# RAM.net
KiCad netlist of a schematic drawn in EAGLE
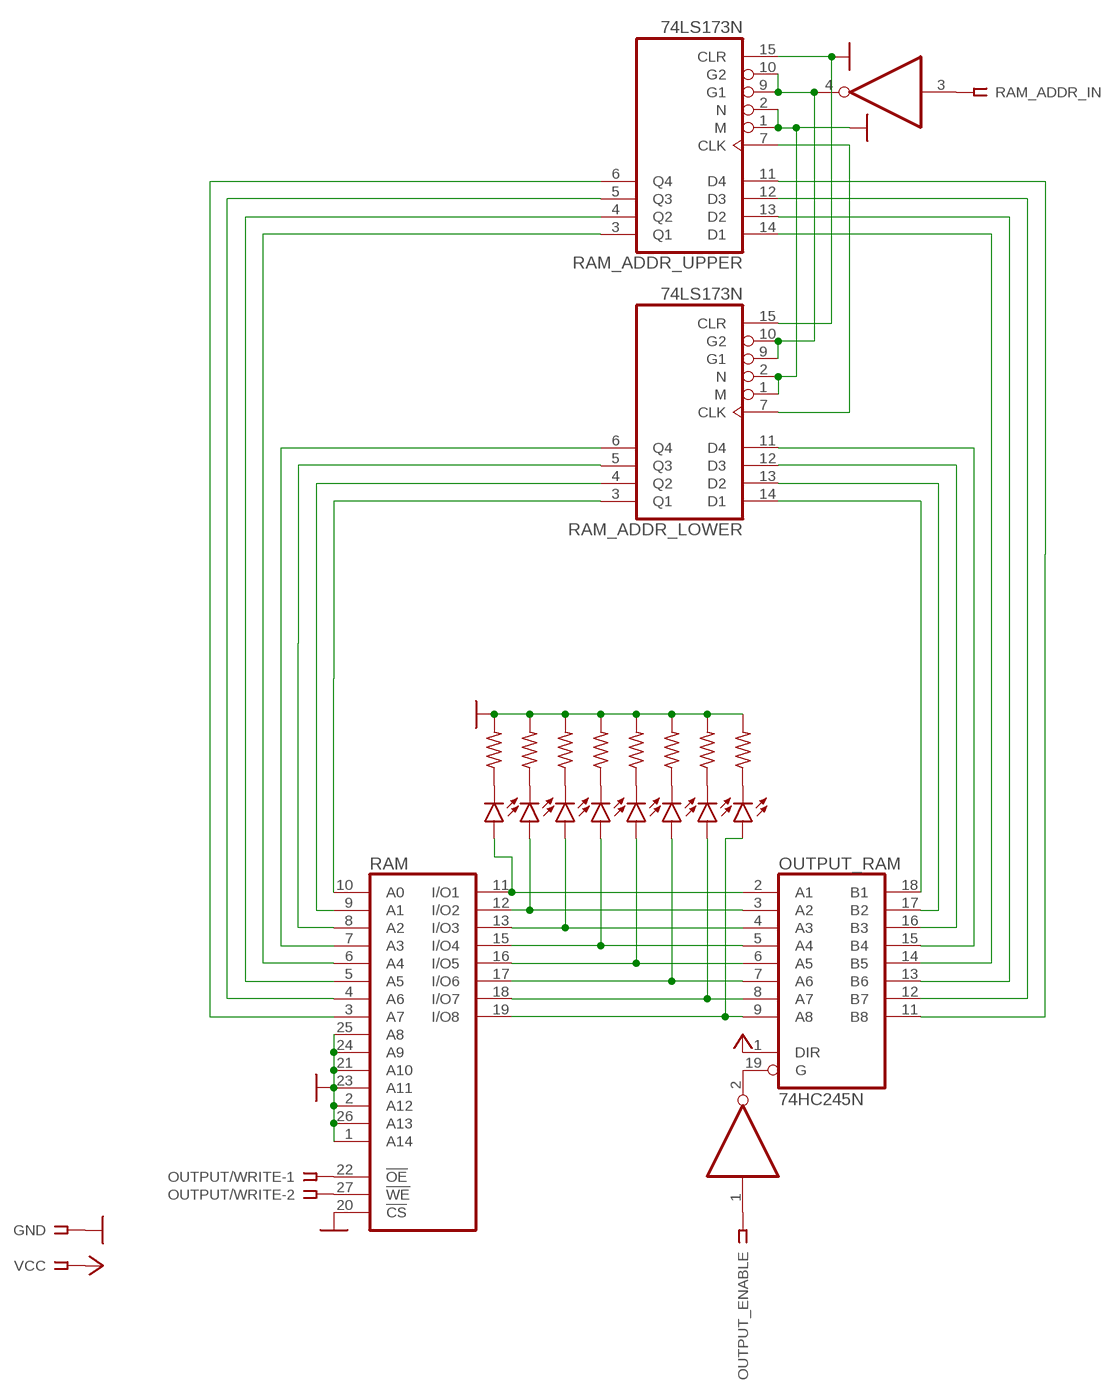
[diagram p0: schematic, sheet 1]

(export (version "E")
  (design (tool "Eeschema 10.0.6"))
  (components
    (comp (ref "GND")
      (value "SSW-101-02-G-S-RA")
      (footprint "eagle-import:SSW-101-02-G-S-RA")
      (fields (field (name "MF") "Samtec Inc."))
      (libsource (lib "eagle-import") (part "SSW-101-02-G-S-RA"))
    )
    (comp (ref "LED1")
      (value "LED3MM")
      (footprint "eagle-import:LED3MM")
      (libsource (lib "eagle-import") (part "LED3MM"))
    )
    (comp (ref "LED2")
      (value "LED3MM")
      (footprint "eagle-import:LED3MM")
      (libsource (lib "eagle-import") (part "LED3MM"))
    )
    (comp (ref "LED3")
      (value "LED3MM")
      (footprint "eagle-import:LED3MM")
      (libsource (lib "eagle-import") (part "LED3MM"))
    )
    (comp (ref "LED4")
      (value "LED3MM")
      (footprint "eagle-import:LED3MM")
      (libsource (lib "eagle-import") (part "LED3MM"))
    )
    (comp (ref "LED5")
      (value "LED3MM")
      (footprint "eagle-import:LED3MM")
      (libsource (lib "eagle-import") (part "LED3MM"))
    )
    (comp (ref "LED6")
      (value "LED3MM")
      (footprint "eagle-import:LED3MM")
      (libsource (lib "eagle-import") (part "LED3MM"))
    )
    (comp (ref "LED7")
      (value "LED3MM")
      (footprint "eagle-import:LED3MM")
      (libsource (lib "eagle-import") (part "LED3MM"))
    )
    (comp (ref "LED8")
      (value "LED3MM")
      (footprint "eagle-import:LED3MM")
      (libsource (lib "eagle-import") (part "LED3MM"))
    )
    (comp (ref "NOT_GATE")
      (value "74LS04N")
      (footprint "eagle-import:DIL14")
      (libsource (lib "eagle-import") (part "7404NLS"))
    )
    (comp (ref "OUTPUT/WRITE")
      (value "SSW-102-02-G-S")
      (footprint "eagle-import:SSW-102-02-G-S")
      (fields (field (name "MF") "Samtec Inc."))
      (libsource (lib "eagle-import") (part "SSW-102-02-G-S"))
    )
    (comp (ref "OUTPUT_ENABLE")
      (value "SSW-101-02-G-S")
      (footprint "eagle-import:SSW-101-02-G-S")
      (fields (field (name "MF") "Samtec Inc."))
      (libsource (lib "eagle-import") (part "SSW-101-02-G-S"))
    )
    (comp (ref "OUTPUT_RAM")
      (value "74HC245N")
      (footprint "eagle-import:DIL20")
      (libsource (lib "eagle-import") (part "74245NHC"))
    )
    (comp (ref "R1")
      (value "R-US_0204/7")
      (footprint "eagle-import:0204_7")
      (libsource (lib "eagle-import") (part "R-US_0204/7"))
    )
    (comp (ref "R2")
      (value "R-US_0204/7")
      (footprint "eagle-import:0204_7")
      (libsource (lib "eagle-import") (part "R-US_0204/7"))
    )
    (comp (ref "R3")
      (value "R-US_0204/7")
      (footprint "eagle-import:0204_7")
      (libsource (lib "eagle-import") (part "R-US_0204/7"))
    )
    (comp (ref "R4")
      (value "R-US_0204/7")
      (footprint "eagle-import:0204_7")
      (libsource (lib "eagle-import") (part "R-US_0204/7"))
    )
    (comp (ref "R5")
      (value "R-US_0204/7")
      (footprint "eagle-import:0204_7")
      (libsource (lib "eagle-import") (part "R-US_0204/7"))
    )
    (comp (ref "R6")
      (value "R-US_0204/7")
      (footprint "eagle-import:0204_7")
      (libsource (lib "eagle-import") (part "R-US_0204/7"))
    )
    (comp (ref "R7")
      (value "R-US_0204/7")
      (footprint "eagle-import:0204_7")
      (libsource (lib "eagle-import") (part "R-US_0204/7"))
    )
    (comp (ref "R8")
      (value "R-US_0204/7")
      (footprint "eagle-import:0204_7")
      (libsource (lib "eagle-import") (part "R-US_0204/7"))
    )
    (comp (ref "RAM")
      (value "71256P")
      (footprint "eagle-import:DIL28-6")
      (libsource (lib "eagle-import") (part "71256P"))
    )
    (comp (ref "RAM_ADDR_IN")
      (value "SSW-101-02-G-S")
      (footprint "eagle-import:SSW-101-02-G-S")
      (fields (field (name "MF") "Samtec Inc."))
      (libsource (lib "eagle-import") (part "SSW-101-02-G-S"))
    )
    (comp (ref "RAM_ADDR_LOWER")
      (value "74LS173N")
      (footprint "eagle-import:DIL16")
      (libsource (lib "eagle-import") (part "74173NLS"))
    )
    (comp (ref "RAM_ADDR_UPPER")
      (value "74LS173N")
      (footprint "eagle-import:DIL16")
      (libsource (lib "eagle-import") (part "74173NLS"))
    )
    (comp (ref "VCC")
      (value "SSW-101-02-G-S-RA")
      (footprint "eagle-import:SSW-101-02-G-S-RA")
      (fields (field (name "MF") "Samtec Inc."))
      (libsource (lib "eagle-import") (part "SSW-101-02-G-S-RA"))
    )
  )
  (nets
    (net (code "1") (name "GND") (class "Default")
      (node (ref "GND") (pin "1") (pinfunction "1_1") (pintype "passive"))
      (node (ref "R1") (pin "2") (pinfunction "2_2") (pintype "passive"))
      (node (ref "R2") (pin "2") (pinfunction "2_2") (pintype "passive"))
      (node (ref "R3") (pin "2") (pinfunction "2_2") (pintype "passive"))
      (node (ref "R4") (pin "2") (pinfunction "2_2") (pintype "passive"))
      (node (ref "R5") (pin "2") (pinfunction "2_2") (pintype "passive"))
      (node (ref "R6") (pin "2") (pinfunction "2_2") (pintype "passive"))
      (node (ref "R7") (pin "2") (pinfunction "2_2") (pintype "passive"))
      (node (ref "R8") (pin "2") (pinfunction "2_2") (pintype "passive"))
      (node (ref "RAM") (pin "1") (pinfunction "A14_1") (pintype "input"))
      (node (ref "RAM") (pin "2") (pinfunction "A12_2") (pintype "input"))
      (node (ref "RAM") (pin "20") (pinfunction "~{CS}_20") (pintype "input"))
      (node (ref "RAM") (pin "21") (pinfunction "A10_21") (pintype "input"))
      (node (ref "RAM") (pin "23") (pinfunction "A11_23") (pintype "input"))
      (node (ref "RAM") (pin "24") (pinfunction "A9_24") (pintype "input"))
      (node (ref "RAM") (pin "25") (pinfunction "A8_25") (pintype "input"))
      (node (ref "RAM") (pin "26") (pinfunction "A13_26") (pintype "input"))
      (node (ref "RAM_ADDR_LOWER") (pin "1") (pinfunction "M_1") (pintype "input"))
      (node (ref "RAM_ADDR_LOWER") (pin "15") (pinfunction "CLR_15") (pintype "input"))
      (node (ref "RAM_ADDR_LOWER") (pin "2") (pinfunction "N_2") (pintype "input"))
      (node (ref "RAM_ADDR_UPPER") (pin "1") (pinfunction "M_1") (pintype "input"))
      (node (ref "RAM_ADDR_UPPER") (pin "15") (pinfunction "CLR_15") (pintype "input"))
      (node (ref "RAM_ADDR_UPPER") (pin "2") (pinfunction "N_2") (pintype "input"))
    )
    (net (code "2") (name "Net-(LED1-C)") (class "Default")
      (node (ref "LED1") (pin "K") (pinfunction "C_K") (pintype "passive"))
      (node (ref "R1") (pin "1") (pinfunction "1_1") (pintype "passive"))
    )
    (net (code "3") (name "Net-(LED2-C)") (class "Default")
      (node (ref "LED2") (pin "K") (pinfunction "C_K") (pintype "passive"))
      (node (ref "R2") (pin "1") (pinfunction "1_1") (pintype "passive"))
    )
    (net (code "4") (name "Net-(LED3-C)") (class "Default")
      (node (ref "LED3") (pin "K") (pinfunction "C_K") (pintype "passive"))
      (node (ref "R3") (pin "1") (pinfunction "1_1") (pintype "passive"))
    )
    (net (code "5") (name "Net-(LED4-C)") (class "Default")
      (node (ref "LED4") (pin "K") (pinfunction "C_K") (pintype "passive"))
      (node (ref "R4") (pin "1") (pinfunction "1_1") (pintype "passive"))
    )
    (net (code "6") (name "Net-(LED5-C)") (class "Default")
      (node (ref "LED5") (pin "K") (pinfunction "C_K") (pintype "passive"))
      (node (ref "R5") (pin "1") (pinfunction "1_1") (pintype "passive"))
    )
    (net (code "7") (name "Net-(LED6-C)") (class "Default")
      (node (ref "LED6") (pin "K") (pinfunction "C_K") (pintype "passive"))
      (node (ref "R6") (pin "1") (pinfunction "1_1") (pintype "passive"))
    )
    (net (code "8") (name "Net-(LED7-C)") (class "Default")
      (node (ref "LED7") (pin "K") (pinfunction "C_K") (pintype "passive"))
      (node (ref "R7") (pin "1") (pinfunction "1_1") (pintype "passive"))
    )
    (net (code "9") (name "Net-(LED8-C)") (class "Default")
      (node (ref "LED8") (pin "K") (pinfunction "C_K") (pintype "passive"))
      (node (ref "R8") (pin "1") (pinfunction "1_1") (pintype "passive"))
    )
    (net (code "10") (name "Net-(NOT_GATEA-I)") (class "Default")
      (node (ref "NOT_GATE") (pin "1") (pinfunction "I_1") (pintype "input"))
      (node (ref "OUTPUT_ENABLE") (pin "1") (pinfunction "1_1") (pintype "passive"))
    )
    (net (code "11") (name "Net-(NOT_GATEA-O)") (class "Default")
      (node (ref "NOT_GATE") (pin "2") (pinfunction "O_2") (pintype "output"))
      (node (ref "OUTPUT_RAM") (pin "19") (pinfunction "G_19") (pintype "input"))
    )
    (net (code "12") (name "Net-(NOT_GATEB-I)") (class "Default")
      (node (ref "NOT_GATE") (pin "3") (pinfunction "I_3") (pintype "input"))
      (node (ref "RAM_ADDR_IN") (pin "1") (pinfunction "1_1") (pintype "passive"))
    )
    (net (code "13") (name "Net-(NOT_GATEB-O)") (class "Default")
      (node (ref "NOT_GATE") (pin "4") (pinfunction "O_4") (pintype "output"))
      (node (ref "RAM_ADDR_LOWER") (pin "10") (pinfunction "G2_10") (pintype "input"))
      (node (ref "RAM_ADDR_LOWER") (pin "9") (pinfunction "G1_9") (pintype "input"))
      (node (ref "RAM_ADDR_UPPER") (pin "10") (pinfunction "G2_10") (pintype "input"))
      (node (ref "RAM_ADDR_UPPER") (pin "9") (pinfunction "G1_9") (pintype "input"))
    )
    (net (code "14") (name "Net-(OUTPUT/WRITEB-1)") (class "Default")
      (node (ref "OUTPUT/WRITE") (pin "2") (pinfunction "1_2") (pintype "passive"))
      (node (ref "RAM") (pin "27") (pinfunction "~{WE}_27") (pintype "input"))
    )
    (net (code "15") (name "Net-(OUTPUT_RAMA-A1)") (class "Default")
      (node (ref "LED8") (pin "A") (pinfunction "A_A") (pintype "passive"))
      (node (ref "OUTPUT_RAM") (pin "2") (pinfunction "A1_2") (pintype "bidirectional"))
      (node (ref "RAM") (pin "11") (pinfunction "I/O1_11") (pintype "bidirectional"))
    )
    (net (code "16") (name "Net-(OUTPUT_RAMA-A2)") (class "Default")
      (node (ref "LED1") (pin "A") (pinfunction "A_A") (pintype "passive"))
      (node (ref "OUTPUT_RAM") (pin "3") (pinfunction "A2_3") (pintype "bidirectional"))
      (node (ref "RAM") (pin "12") (pinfunction "I/O2_12") (pintype "bidirectional"))
    )
    (net (code "17") (name "Net-(OUTPUT_RAMA-A3)") (class "Default")
      (node (ref "LED2") (pin "A") (pinfunction "A_A") (pintype "passive"))
      (node (ref "OUTPUT_RAM") (pin "4") (pinfunction "A3_4") (pintype "bidirectional"))
      (node (ref "RAM") (pin "13") (pinfunction "I/O3_13") (pintype "bidirectional"))
    )
    (net (code "18") (name "Net-(OUTPUT_RAMA-A4)") (class "Default")
      (node (ref "LED3") (pin "A") (pinfunction "A_A") (pintype "passive"))
      (node (ref "OUTPUT_RAM") (pin "5") (pinfunction "A4_5") (pintype "bidirectional"))
      (node (ref "RAM") (pin "15") (pinfunction "I/O4_15") (pintype "bidirectional"))
    )
    (net (code "19") (name "Net-(OUTPUT_RAMA-A5)") (class "Default")
      (node (ref "LED4") (pin "A") (pinfunction "A_A") (pintype "passive"))
      (node (ref "OUTPUT_RAM") (pin "6") (pinfunction "A5_6") (pintype "bidirectional"))
      (node (ref "RAM") (pin "16") (pinfunction "I/O5_16") (pintype "bidirectional"))
    )
    (net (code "20") (name "Net-(OUTPUT_RAMA-A6)") (class "Default")
      (node (ref "LED5") (pin "A") (pinfunction "A_A") (pintype "passive"))
      (node (ref "OUTPUT_RAM") (pin "7") (pinfunction "A6_7") (pintype "bidirectional"))
      (node (ref "RAM") (pin "17") (pinfunction "I/O6_17") (pintype "bidirectional"))
    )
    (net (code "21") (name "Net-(OUTPUT_RAMA-A7)") (class "Default")
      (node (ref "LED6") (pin "A") (pinfunction "A_A") (pintype "passive"))
      (node (ref "OUTPUT_RAM") (pin "8") (pinfunction "A7_8") (pintype "bidirectional"))
      (node (ref "RAM") (pin "18") (pinfunction "I/O7_18") (pintype "bidirectional"))
    )
    (net (code "22") (name "Net-(OUTPUT_RAMA-A8)") (class "Default")
      (node (ref "LED7") (pin "A") (pinfunction "A_A") (pintype "passive"))
      (node (ref "OUTPUT_RAM") (pin "9") (pinfunction "A8_9") (pintype "bidirectional"))
      (node (ref "RAM") (pin "19") (pinfunction "I/O8_19") (pintype "bidirectional"))
    )
    (net (code "23") (name "Net-(OUTPUT_RAMA-B1)") (class "Default")
      (node (ref "OUTPUT_RAM") (pin "18") (pinfunction "B1_18") (pintype "bidirectional"))
      (node (ref "RAM_ADDR_LOWER") (pin "14") (pinfunction "D1_14") (pintype "input"))
    )
    (net (code "24") (name "Net-(OUTPUT_RAMA-B2)") (class "Default")
      (node (ref "OUTPUT_RAM") (pin "17") (pinfunction "B2_17") (pintype "bidirectional"))
      (node (ref "RAM_ADDR_LOWER") (pin "13") (pinfunction "D2_13") (pintype "input"))
    )
    (net (code "25") (name "Net-(OUTPUT_RAMA-B3)") (class "Default")
      (node (ref "OUTPUT_RAM") (pin "16") (pinfunction "B3_16") (pintype "bidirectional"))
      (node (ref "RAM_ADDR_LOWER") (pin "12") (pinfunction "D3_12") (pintype "input"))
    )
    (net (code "26") (name "Net-(OUTPUT_RAMA-B4)") (class "Default")
      (node (ref "OUTPUT_RAM") (pin "15") (pinfunction "B4_15") (pintype "bidirectional"))
      (node (ref "RAM_ADDR_LOWER") (pin "11") (pinfunction "D4_11") (pintype "input"))
    )
    (net (code "27") (name "Net-(OUTPUT_RAMA-B5)") (class "Default")
      (node (ref "OUTPUT_RAM") (pin "14") (pinfunction "B5_14") (pintype "bidirectional"))
      (node (ref "RAM_ADDR_UPPER") (pin "14") (pinfunction "D1_14") (pintype "input"))
    )
    (net (code "28") (name "Net-(OUTPUT_RAMA-B6)") (class "Default")
      (node (ref "OUTPUT_RAM") (pin "13") (pinfunction "B6_13") (pintype "bidirectional"))
      (node (ref "RAM_ADDR_UPPER") (pin "13") (pinfunction "D2_13") (pintype "input"))
    )
    (net (code "29") (name "Net-(OUTPUT_RAMA-B7)") (class "Default")
      (node (ref "OUTPUT_RAM") (pin "12") (pinfunction "B7_12") (pintype "bidirectional"))
      (node (ref "RAM_ADDR_UPPER") (pin "12") (pinfunction "D3_12") (pintype "input"))
    )
    (net (code "30") (name "Net-(OUTPUT_RAMA-B8)") (class "Default")
      (node (ref "OUTPUT_RAM") (pin "11") (pinfunction "B8_11") (pintype "bidirectional"))
      (node (ref "RAM_ADDR_UPPER") (pin "11") (pinfunction "D4_11") (pintype "input"))
    )
    (net (code "31") (name "Net-(RAMA-A0)") (class "Default")
      (node (ref "RAM") (pin "10") (pinfunction "A0_10") (pintype "input"))
      (node (ref "RAM_ADDR_LOWER") (pin "3") (pinfunction "Q1_3") (pintype "tri_state"))
    )
    (net (code "32") (name "Net-(RAMA-A1)") (class "Default")
      (node (ref "RAM") (pin "9") (pinfunction "A1_9") (pintype "input"))
      (node (ref "RAM_ADDR_LOWER") (pin "4") (pinfunction "Q2_4") (pintype "tri_state"))
    )
    (net (code "33") (name "Net-(RAMA-A2)") (class "Default")
      (node (ref "RAM") (pin "8") (pinfunction "A2_8") (pintype "input"))
      (node (ref "RAM_ADDR_LOWER") (pin "5") (pinfunction "Q3_5") (pintype "tri_state"))
    )
    (net (code "34") (name "Net-(RAMA-A3)") (class "Default")
      (node (ref "RAM") (pin "7") (pinfunction "A3_7") (pintype "input"))
      (node (ref "RAM_ADDR_LOWER") (pin "6") (pinfunction "Q4_6") (pintype "tri_state"))
    )
    (net (code "35") (name "Net-(RAMA-A4)") (class "Default")
      (node (ref "RAM") (pin "6") (pinfunction "A4_6") (pintype "input"))
      (node (ref "RAM_ADDR_UPPER") (pin "3") (pinfunction "Q1_3") (pintype "tri_state"))
    )
    (net (code "36") (name "Net-(RAMA-A5)") (class "Default")
      (node (ref "RAM") (pin "5") (pinfunction "A5_5") (pintype "input"))
      (node (ref "RAM_ADDR_UPPER") (pin "4") (pinfunction "Q2_4") (pintype "tri_state"))
    )
    (net (code "37") (name "Net-(RAMA-A6)") (class "Default")
      (node (ref "RAM") (pin "4") (pinfunction "A6_4") (pintype "input"))
      (node (ref "RAM_ADDR_UPPER") (pin "5") (pinfunction "Q3_5") (pintype "tri_state"))
    )
    (net (code "38") (name "Net-(RAMA-A7)") (class "Default")
      (node (ref "RAM") (pin "3") (pinfunction "A7_3") (pintype "input"))
      (node (ref "RAM_ADDR_UPPER") (pin "6") (pinfunction "Q4_6") (pintype "tri_state"))
    )
    (net (code "39") (name "Net-(RAMA-~{OE})") (class "Default")
      (node (ref "OUTPUT/WRITE") (pin "1") (pinfunction "1_1") (pintype "passive"))
      (node (ref "RAM") (pin "22") (pinfunction "~{OE}_22") (pintype "input"))
    )
    (net (code "40") (name "Net-(RAM_ADDR_LOWERA-CLK)") (class "Default")
      (node (ref "RAM_ADDR_LOWER") (pin "7") (pinfunction "CLK_7") (pintype "input"))
      (node (ref "RAM_ADDR_UPPER") (pin "7") (pinfunction "CLK_7") (pintype "input"))
    )
    (net (code "41") (name "VCC") (class "Default")
      (node (ref "OUTPUT_RAM") (pin "1") (pinfunction "DIR_1") (pintype "input"))
      (node (ref "VCC") (pin "1") (pinfunction "1_1") (pintype "passive"))
    )
  )
)
